# M-LVDS_PHY.net
KiCad netlist of a schematic drawn in Altium Designer
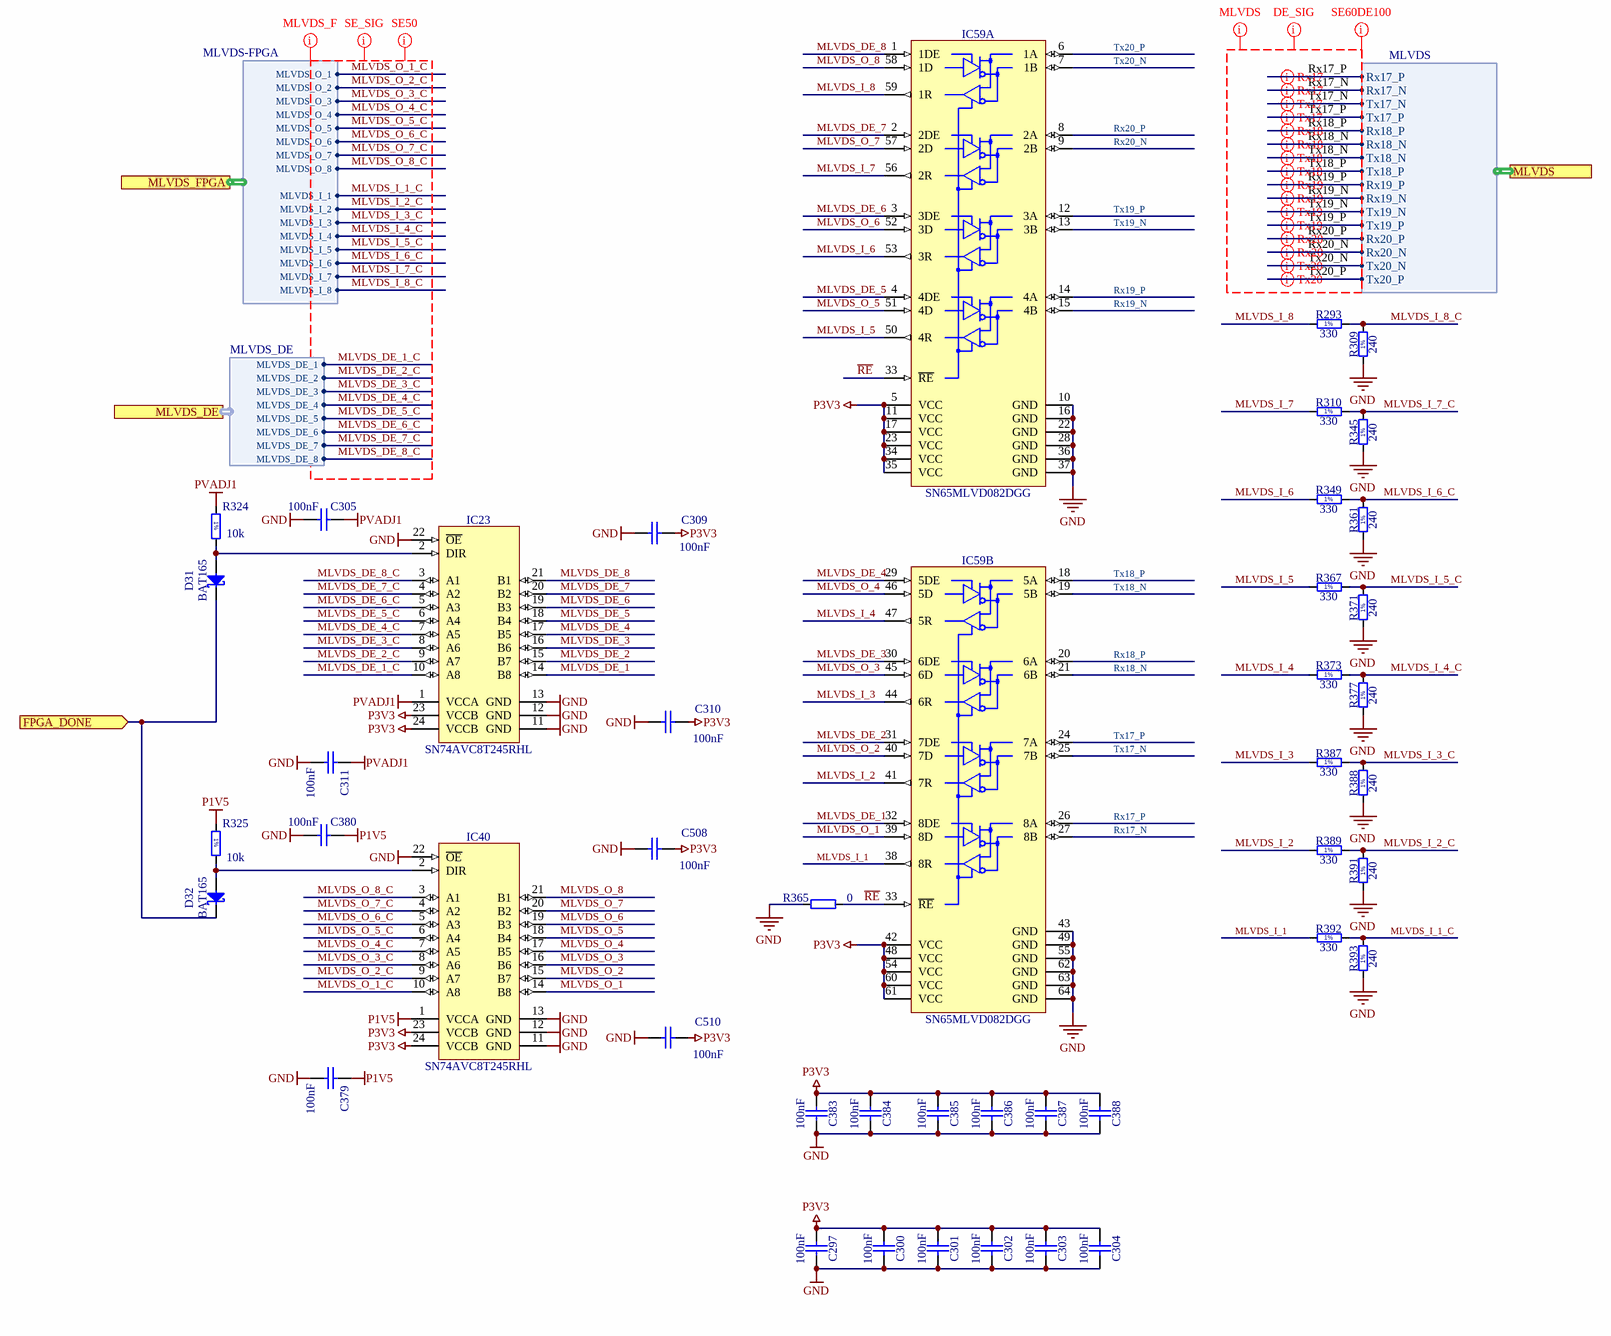
[diagram p0: M-LVDS PHY.SchDoc]

(export (version "E")
  (design (tool "Eeschema 10.0.6"))
  (components
    (comp (ref "C297")
      (value "100nF")
      (footprint "CAPC0603X33N")
      (description "Non-polarised capacitor")
      (fields
        (field (name "PART NUMBER") "CC0201_100NF_6.3V_10%_X5R")
        (field (name "VOLTAGE") "6.3V")
        (field (name "AUTHOR") "CERN DEM JLC")
      )
      (libsource (lib "Capacitors") (part "Capacitor - non polarized"))
    )
    (comp (ref "C300")
      (value "100nF")
      (footprint "CAPC0603X33N")
      (description "Non-polarised capacitor")
      (fields
        (field (name "PART NUMBER") "CC0201_100NF_6.3V_10%_X5R")
        (field (name "VOLTAGE") "6.3V")
        (field (name "AUTHOR") "CERN DEM JLC")
      )
      (libsource (lib "Capacitors") (part "Capacitor - non polarized"))
    )
    (comp (ref "C301")
      (value "100nF")
      (footprint "CAPC0603X33N")
      (description "Non-polarised capacitor")
      (fields
        (field (name "PART NUMBER") "CC0201_100NF_6.3V_10%_X5R")
        (field (name "VOLTAGE") "6.3V")
        (field (name "AUTHOR") "CERN DEM JLC")
      )
      (libsource (lib "Capacitors") (part "Capacitor - non polarized"))
    )
    (comp (ref "C302")
      (value "100nF")
      (footprint "CAPC0603X33N")
      (description "Non-polarised capacitor")
      (fields
        (field (name "PART NUMBER") "CC0201_100NF_6.3V_10%_X5R")
        (field (name "VOLTAGE") "6.3V")
        (field (name "AUTHOR") "CERN DEM JLC")
      )
      (libsource (lib "Capacitors") (part "Capacitor - non polarized"))
    )
    (comp (ref "C303")
      (value "100nF")
      (footprint "CAPC0603X33N")
      (description "Non-polarised capacitor")
      (fields
        (field (name "PART NUMBER") "CC0201_100NF_6.3V_10%_X5R")
        (field (name "VOLTAGE") "6.3V")
        (field (name "AUTHOR") "CERN DEM JLC")
      )
      (libsource (lib "Capacitors") (part "Capacitor - non polarized"))
    )
    (comp (ref "C304")
      (value "100nF")
      (footprint "CAPC0603X33N")
      (description "Non-polarised capacitor")
      (fields
        (field (name "PART NUMBER") "CC0201_100NF_6.3V_10%_X5R")
        (field (name "VOLTAGE") "6.3V")
        (field (name "AUTHOR") "CERN DEM JLC")
      )
      (libsource (lib "Capacitors") (part "Capacitor - non polarized"))
    )
    (comp (ref "C305")
      (value "100nF")
      (footprint "CAPC0603X33N")
      (description "Non-polarised capacitor")
      (fields
        (field (name "PART NUMBER") "CC0201_100NF_6.3V_10%_X5R")
        (field (name "VOLTAGE") "6.3V")
        (field (name "AUTHOR") "CERN DEM JLC")
      )
      (libsource (lib "Capacitors") (part "Capacitor - non polarized"))
    )
    (comp (ref "C309")
      (value "100nF")
      (footprint "CAPC0603X33N")
      (description "Non-polarised capacitor")
      (fields
        (field (name "PART NUMBER") "CC0201_100NF_6.3V_10%_X5R")
        (field (name "VOLTAGE") "6.3V")
        (field (name "AUTHOR") "CERN DEM JLC")
      )
      (libsource (lib "Capacitors") (part "Capacitor - non polarized"))
    )
    (comp (ref "C310")
      (value "100nF")
      (footprint "CAPC0603X33N")
      (description "Non-polarised capacitor")
      (fields
        (field (name "PART NUMBER") "CC0201_100NF_6.3V_10%_X5R")
        (field (name "VOLTAGE") "6.3V")
        (field (name "AUTHOR") "CERN DEM JLC")
      )
      (libsource (lib "Capacitors") (part "Capacitor - non polarized"))
    )
    (comp (ref "C311")
      (value "100nF")
      (footprint "CAPC0603X33N")
      (description "Non-polarised capacitor")
      (fields
        (field (name "PART NUMBER") "CC0201_100NF_6.3V_10%_X5R")
        (field (name "VOLTAGE") "6.3V")
        (field (name "AUTHOR") "CERN DEM JLC")
      )
      (libsource (lib "Capacitors") (part "Capacitor - non polarized"))
    )
    (comp (ref "C379")
      (value "100nF")
      (footprint "CAPC0603X33N")
      (description "Non-polarised capacitor")
      (fields
        (field (name "PART NUMBER") "CC0201_100NF_6.3V_10%_X5R")
        (field (name "VOLTAGE") "6.3V")
        (field (name "AUTHOR") "CERN DEM JLC")
      )
      (libsource (lib "Capacitors") (part "Capacitor - non polarized"))
    )
    (comp (ref "C380")
      (value "100nF")
      (footprint "CAPC0603X33N")
      (description "Non-polarised capacitor")
      (fields
        (field (name "PART NUMBER") "CC0201_100NF_6.3V_10%_X5R")
        (field (name "VOLTAGE") "6.3V")
        (field (name "AUTHOR") "CERN DEM JLC")
      )
      (libsource (lib "Capacitors") (part "Capacitor - non polarized"))
    )
    (comp (ref "C383")
      (value "100nF")
      (footprint "CAPC0603X33N")
      (description "Non-polarised capacitor")
      (fields
        (field (name "PART NUMBER") "CC0201_100NF_6.3V_10%_X5R")
        (field (name "VOLTAGE") "6.3V")
        (field (name "AUTHOR") "CERN DEM JLC")
      )
      (libsource (lib "Capacitors") (part "Capacitor - non polarized"))
    )
    (comp (ref "C384")
      (value "100nF")
      (footprint "CAPC0603X33N")
      (description "Non-polarised capacitor")
      (fields
        (field (name "PART NUMBER") "CC0201_100NF_6.3V_10%_X5R")
        (field (name "VOLTAGE") "6.3V")
        (field (name "AUTHOR") "CERN DEM JLC")
      )
      (libsource (lib "Capacitors") (part "Capacitor - non polarized"))
    )
    (comp (ref "C385")
      (value "100nF")
      (footprint "CAPC0603X33N")
      (description "Non-polarised capacitor")
      (fields
        (field (name "PART NUMBER") "CC0201_100NF_6.3V_10%_X5R")
        (field (name "VOLTAGE") "6.3V")
        (field (name "AUTHOR") "CERN DEM JLC")
      )
      (libsource (lib "Capacitors") (part "Capacitor - non polarized"))
    )
    (comp (ref "C386")
      (value "100nF")
      (footprint "CAPC0603X33N")
      (description "Non-polarised capacitor")
      (fields
        (field (name "PART NUMBER") "CC0201_100NF_6.3V_10%_X5R")
        (field (name "VOLTAGE") "6.3V")
        (field (name "AUTHOR") "CERN DEM JLC")
      )
      (libsource (lib "Capacitors") (part "Capacitor - non polarized"))
    )
    (comp (ref "C387")
      (value "100nF")
      (footprint "CAPC0603X33N")
      (description "Non-polarised capacitor")
      (fields
        (field (name "PART NUMBER") "CC0201_100NF_6.3V_10%_X5R")
        (field (name "VOLTAGE") "6.3V")
        (field (name "AUTHOR") "CERN DEM JLC")
      )
      (libsource (lib "Capacitors") (part "Capacitor - non polarized"))
    )
    (comp (ref "C388")
      (value "100nF")
      (footprint "CAPC0603X33N")
      (description "Non-polarised capacitor")
      (fields
        (field (name "PART NUMBER") "CC0201_100NF_6.3V_10%_X5R")
        (field (name "VOLTAGE") "6.3V")
        (field (name "AUTHOR") "CERN DEM JLC")
      )
      (libsource (lib "Capacitors") (part "Capacitor - non polarized"))
    )
    (comp (ref "C508")
      (value "100nF")
      (footprint "CAPC0603X33N")
      (description "Non-polarised capacitor")
      (fields
        (field (name "PART NUMBER") "CC0201_100NF_6.3V_10%_X5R")
        (field (name "VOLTAGE") "6.3V")
        (field (name "AUTHOR") "CERN DEM JLC")
      )
      (libsource (lib "Capacitors") (part "Capacitor - non polarized"))
    )
    (comp (ref "C510")
      (value "100nF")
      (footprint "CAPC0603X33N")
      (description "Non-polarised capacitor")
      (fields
        (field (name "PART NUMBER") "CC0201_100NF_6.3V_10%_X5R")
        (field (name "VOLTAGE") "6.3V")
        (field (name "AUTHOR") "CERN DEM JLC")
      )
      (libsource (lib "Capacitors") (part "Capacitor - non polarized"))
    )
    (comp (ref "D31")
      (value "BAT165")
      (footprint "SOD2512X110N")
      (description "Schottky Diode")
      (fields
        (field (name "MANUFACTURER") "INFINEON")
        (field (name "VOLTAGE") "40V")
        (field (name "AUTHOR") "CERN DEM JLC")
      )
      (libsource (lib "ICs And Semiconductors") (part "Diode Schottky"))
    )
    (comp (ref "D32")
      (value "BAT165")
      (footprint "SOD2512X110N")
      (description "Schottky Diode")
      (fields
        (field (name "MANUFACTURER") "INFINEON")
        (field (name "VOLTAGE") "40V")
        (field (name "AUTHOR") "CERN DEM JLC")
      )
      (libsource (lib "ICs And Semiconductors") (part "Diode Schottky"))
    )
    (comp (ref "IC23")
      (value "SN74AVC8T245RHL")
      (footprint "TEXAS_RHL (S-PVQFN-N24)")
      (description "8-Bit Dual-Supply Bus Transceiver With Configurable Voltage Translation and 3-State Outputs")
      (fields (field (name "MANUFACTURER") "TEXAS INSTRUMENTS") (field (name "AUTHOR") "CERN DEM MR"))
      (libsource (lib "ICs And Semiconductors") (part "748T245"))
    )
    (comp (ref "IC40")
      (value "SN74AVC8T245RHL")
      (footprint "TEXAS_RHL (S-PVQFN-N24)")
      (description "8-Bit Dual-Supply Bus Transceiver With Configurable Voltage Translation and 3-State Outputs")
      (fields (field (name "MANUFACTURER") "TEXAS INSTRUMENTS") (field (name "AUTHOR") "CERN DEM MR"))
      (libsource (lib "ICs And Semiconductors") (part "748T245"))
    )
    (comp (ref "IC59")
      (value "SN65MLVD082DGG")
      (footprint "SOP50P810X120-64N")
      (description "8-Channel Half-Duplex M-LVDS Line Transceiver")
      (fields (field (name "MANUFACTURER") "TEXAS INSTRUMENTS") (field (name "AUTHOR") "CERN DEM BC"))
      (libsource (lib "ICs And Semiconductors") (part "SN65MLVD082"))
    )
    (comp (ref "R293")
      (value "330")
      (footprint "RESC1005X40N")
      (description "Resistor - 1%")
      (fields
        (field (name "PART NUMBER") "R0402_330R_1%_0.0625W_100PPM")
        (field (name "POWER") "0.0625W")
        (field (name "AUTHOR") "CERN DEM JLC")
      )
      (libsource (lib "Resistors") (part "Resistor - 1%"))
    )
    (comp (ref "R309")
      (value "240")
      (footprint "RESC1005X40N")
      (description "Resistor - 1%")
      (fields
        (field (name "PART NUMBER") "R0402_240R_1%_0.0625W_100PPM")
        (field (name "POWER") "0.0625W")
        (field (name "AUTHOR") "CERN DEM JLC")
      )
      (libsource (lib "Resistors") (part "Resistor - 1%"))
    )
    (comp (ref "R310")
      (value "330")
      (footprint "RESC1005X40N")
      (description "Resistor - 1%")
      (fields
        (field (name "PART NUMBER") "R0402_330R_1%_0.0625W_100PPM")
        (field (name "POWER") "0.0625W")
        (field (name "AUTHOR") "CERN DEM JLC")
      )
      (libsource (lib "Resistors") (part "Resistor - 1%"))
    )
    (comp (ref "R324")
      (value "10k")
      (footprint "RESC1005X40N")
      (description "Resistor - 1%")
      (fields
        (field (name "PART NUMBER") "R0402_10K_1%_0.0625W_100PPM")
        (field (name "POWER") "0.0625W")
        (field (name "AUTHOR") "CERN DEM JLC")
      )
      (libsource (lib "Resistors") (part "Resistor - 1%"))
    )
    (comp (ref "R325")
      (value "10k")
      (footprint "RESC1005X40N")
      (description "Resistor - 1%")
      (fields
        (field (name "PART NUMBER") "R0402_10K_1%_0.0625W_100PPM")
        (field (name "POWER") "0.0625W")
        (field (name "AUTHOR") "CERN DEM JLC")
      )
      (libsource (lib "Resistors") (part "Resistor - 1%"))
    )
    (comp (ref "R345")
      (value "240")
      (footprint "RESC1005X40N")
      (description "Resistor - 1%")
      (fields
        (field (name "PART NUMBER") "R0402_240R_1%_0.0625W_100PPM")
        (field (name "POWER") "0.0625W")
        (field (name "AUTHOR") "CERN DEM JLC")
      )
      (libsource (lib "Resistors") (part "Resistor - 1%"))
    )
    (comp (ref "R349")
      (value "330")
      (footprint "RESC1005X40N")
      (description "Resistor - 1%")
      (fields
        (field (name "PART NUMBER") "R0402_330R_1%_0.0625W_100PPM")
        (field (name "POWER") "0.0625W")
        (field (name "AUTHOR") "CERN DEM JLC")
      )
      (libsource (lib "Resistors") (part "Resistor - 1%"))
    )
    (comp (ref "R361")
      (value "240")
      (footprint "RESC1005X40N")
      (description "Resistor - 1%")
      (fields
        (field (name "PART NUMBER") "R0402_240R_1%_0.0625W_100PPM")
        (field (name "POWER") "0.0625W")
        (field (name "AUTHOR") "CERN DEM JLC")
      )
      (libsource (lib "Resistors") (part "Resistor - 1%"))
    )
    (comp (ref "R365")
      (value "0")
      (footprint "RESC0603X28N")
      (description "Resistor")
      (fields
        (field (name "PART NUMBER") "R0201_0R_JUMPER")
        (field (name "MANUFACTURER") "GENERIC")
        (field (name "AUTHOR") "CERN DEM JLC")
      )
      (libsource (lib "Resistors") (part "Resistor"))
    )
    (comp (ref "R367")
      (value "330")
      (footprint "RESC1005X40N")
      (description "Resistor - 1%")
      (fields
        (field (name "PART NUMBER") "R0402_330R_1%_0.0625W_100PPM")
        (field (name "POWER") "0.0625W")
        (field (name "AUTHOR") "CERN DEM JLC")
      )
      (libsource (lib "Resistors") (part "Resistor - 1%"))
    )
    (comp (ref "R371")
      (value "240")
      (footprint "RESC1005X40N")
      (description "Resistor - 1%")
      (fields
        (field (name "PART NUMBER") "R0402_240R_1%_0.0625W_100PPM")
        (field (name "POWER") "0.0625W")
        (field (name "AUTHOR") "CERN DEM JLC")
      )
      (libsource (lib "Resistors") (part "Resistor - 1%"))
    )
    (comp (ref "R373")
      (value "330")
      (footprint "RESC1005X40N")
      (description "Resistor - 1%")
      (fields
        (field (name "PART NUMBER") "R0402_330R_1%_0.0625W_100PPM")
        (field (name "POWER") "0.0625W")
        (field (name "AUTHOR") "CERN DEM JLC")
      )
      (libsource (lib "Resistors") (part "Resistor - 1%"))
    )
    (comp (ref "R377")
      (value "240")
      (footprint "RESC1005X40N")
      (description "Resistor - 1%")
      (fields
        (field (name "PART NUMBER") "R0402_240R_1%_0.0625W_100PPM")
        (field (name "POWER") "0.0625W")
        (field (name "AUTHOR") "CERN DEM JLC")
      )
      (libsource (lib "Resistors") (part "Resistor - 1%"))
    )
    (comp (ref "R387")
      (value "330")
      (footprint "RESC1005X40N")
      (description "Resistor - 1%")
      (fields
        (field (name "PART NUMBER") "R0402_330R_1%_0.0625W_100PPM")
        (field (name "POWER") "0.0625W")
        (field (name "AUTHOR") "CERN DEM JLC")
      )
      (libsource (lib "Resistors") (part "Resistor - 1%"))
    )
    (comp (ref "R388")
      (value "240")
      (footprint "RESC1005X40N")
      (description "Resistor - 1%")
      (fields
        (field (name "PART NUMBER") "R0402_240R_1%_0.0625W_100PPM")
        (field (name "POWER") "0.0625W")
        (field (name "AUTHOR") "CERN DEM JLC")
      )
      (libsource (lib "Resistors") (part "Resistor - 1%"))
    )
    (comp (ref "R389")
      (value "330")
      (footprint "RESC1005X40N")
      (description "Resistor - 1%")
      (fields
        (field (name "PART NUMBER") "R0402_330R_1%_0.0625W_100PPM")
        (field (name "POWER") "0.0625W")
        (field (name "AUTHOR") "CERN DEM JLC")
      )
      (libsource (lib "Resistors") (part "Resistor - 1%"))
    )
    (comp (ref "R391")
      (value "240")
      (footprint "RESC1005X40N")
      (description "Resistor - 1%")
      (fields
        (field (name "PART NUMBER") "R0402_240R_1%_0.0625W_100PPM")
        (field (name "POWER") "0.0625W")
        (field (name "AUTHOR") "CERN DEM JLC")
      )
      (libsource (lib "Resistors") (part "Resistor - 1%"))
    )
    (comp (ref "R392")
      (value "330")
      (footprint "RESC1005X40N")
      (description "Resistor - 1%")
      (fields
        (field (name "PART NUMBER") "R0402_330R_1%_0.0625W_100PPM")
        (field (name "POWER") "0.0625W")
        (field (name "AUTHOR") "CERN DEM JLC")
      )
      (libsource (lib "Resistors") (part "Resistor - 1%"))
    )
    (comp (ref "R393")
      (value "240")
      (footprint "RESC1005X40N")
      (description "Resistor - 1%")
      (fields
        (field (name "PART NUMBER") "R0402_240R_1%_0.0625W_100PPM")
        (field (name "POWER") "0.0625W")
        (field (name "AUTHOR") "CERN DEM JLC")
      )
      (libsource (lib "Resistors") (part "Resistor - 1%"))
    )
  )
  (nets
    (net (code "4") (name "/FPGA_DONE") (class "Default")
      (node (ref "D31") (pin "1") (pinfunction "C_1") (pintype "passive"))
      (node (ref "D32") (pin "1") (pinfunction "C_1") (pintype "passive"))
    )
    (net (code "5") (name "/MLVDS_DE_1") (class "Default")
      (node (ref "IC23") (pin "14") (pinfunction "B8_14") (pintype "bidirectional"))
      (node (ref "IC59") (pin "32") (pinfunction "8DE_32") (pintype "input"))
    )
    (net (code "6") (name "/MLVDS_DE_1_C") (class "Default")
      (node (ref "IC23") (pin "10") (pinfunction "A8_10") (pintype "bidirectional"))
    )
    (net (code "7") (name "/MLVDS_DE_2") (class "Default")
      (node (ref "IC23") (pin "15") (pinfunction "B7_15") (pintype "bidirectional"))
      (node (ref "IC59") (pin "31") (pinfunction "7DE_31") (pintype "input"))
    )
    (net (code "8") (name "/MLVDS_DE_2_C") (class "Default")
      (node (ref "IC23") (pin "9") (pinfunction "A7_9") (pintype "bidirectional"))
    )
    (net (code "9") (name "/MLVDS_DE_3") (class "Default")
      (node (ref "IC23") (pin "16") (pinfunction "B6_16") (pintype "bidirectional"))
      (node (ref "IC59") (pin "30") (pinfunction "6DE_30") (pintype "input"))
    )
    (net (code "10") (name "/MLVDS_DE_3_C") (class "Default")
      (node (ref "IC23") (pin "8") (pinfunction "A6_8") (pintype "bidirectional"))
    )
    (net (code "11") (name "/MLVDS_DE_4") (class "Default")
      (node (ref "IC23") (pin "17") (pinfunction "B5_17") (pintype "bidirectional"))
      (node (ref "IC59") (pin "29") (pinfunction "5DE_29") (pintype "input"))
    )
    (net (code "12") (name "/MLVDS_DE_4_C") (class "Default")
      (node (ref "IC23") (pin "7") (pinfunction "A5_7") (pintype "bidirectional"))
    )
    (net (code "13") (name "/MLVDS_DE_5") (class "Default")
      (node (ref "IC23") (pin "18") (pinfunction "B4_18") (pintype "bidirectional"))
      (node (ref "IC59") (pin "4") (pinfunction "4DE_4") (pintype "input"))
    )
    (net (code "14") (name "/MLVDS_DE_5_C") (class "Default")
      (node (ref "IC23") (pin "6") (pinfunction "A4_6") (pintype "bidirectional"))
    )
    (net (code "15") (name "/MLVDS_DE_6") (class "Default")
      (node (ref "IC23") (pin "19") (pinfunction "B3_19") (pintype "bidirectional"))
      (node (ref "IC59") (pin "3") (pinfunction "3DE_3") (pintype "input"))
    )
    (net (code "16") (name "/MLVDS_DE_6_C") (class "Default")
      (node (ref "IC23") (pin "5") (pinfunction "A3_5") (pintype "bidirectional"))
    )
    (net (code "17") (name "/MLVDS_DE_7") (class "Default")
      (node (ref "IC23") (pin "20") (pinfunction "B2_20") (pintype "bidirectional"))
      (node (ref "IC59") (pin "2") (pinfunction "2DE_2") (pintype "input"))
    )
    (net (code "18") (name "/MLVDS_DE_7_C") (class "Default")
      (node (ref "IC23") (pin "4") (pinfunction "A2_4") (pintype "bidirectional"))
    )
    (net (code "19") (name "/MLVDS_DE_8") (class "Default")
      (node (ref "IC23") (pin "21") (pinfunction "B1_21") (pintype "bidirectional"))
      (node (ref "IC59") (pin "1") (pinfunction "1DE_1") (pintype "input"))
    )
    (net (code "20") (name "/MLVDS_DE_8_C") (class "Default")
      (node (ref "IC23") (pin "3") (pinfunction "A1_3") (pintype "bidirectional"))
    )
    (net (code "21") (name "/MLVDS_I_1") (class "Default")
      (node (ref "IC59") (pin "38") (pinfunction "8R_38") (pintype "output"))
      (node (ref "R392") (pin "1") (pinfunction "1_1") (pintype "passive"))
    )
    (net (code "22") (name "/MLVDS_I_1_C") (class "Default")
      (node (ref "R392") (pin "2") (pinfunction "2_2") (pintype "passive"))
      (node (ref "R393") (pin "2") (pinfunction "2_2") (pintype "passive"))
    )
    (net (code "23") (name "/MLVDS_I_2") (class "Default")
      (node (ref "IC59") (pin "41") (pinfunction "7R_41") (pintype "output"))
      (node (ref "R389") (pin "1") (pinfunction "1_1") (pintype "passive"))
    )
    (net (code "24") (name "/MLVDS_I_2_C") (class "Default")
      (node (ref "R389") (pin "2") (pinfunction "2_2") (pintype "passive"))
      (node (ref "R391") (pin "2") (pinfunction "2_2") (pintype "passive"))
    )
    (net (code "25") (name "/MLVDS_I_3") (class "Default")
      (node (ref "IC59") (pin "44") (pinfunction "6R_44") (pintype "output"))
      (node (ref "R387") (pin "1") (pinfunction "1_1") (pintype "passive"))
    )
    (net (code "26") (name "/MLVDS_I_3_C") (class "Default")
      (node (ref "R387") (pin "2") (pinfunction "2_2") (pintype "passive"))
      (node (ref "R388") (pin "2") (pinfunction "2_2") (pintype "passive"))
    )
    (net (code "27") (name "/MLVDS_I_4") (class "Default")
      (node (ref "IC59") (pin "47") (pinfunction "5R_47") (pintype "output"))
      (node (ref "R373") (pin "1") (pinfunction "1_1") (pintype "passive"))
    )
    (net (code "28") (name "/MLVDS_I_4_C") (class "Default")
      (node (ref "R373") (pin "2") (pinfunction "2_2") (pintype "passive"))
      (node (ref "R377") (pin "2") (pinfunction "2_2") (pintype "passive"))
    )
    (net (code "29") (name "/MLVDS_I_5") (class "Default")
      (node (ref "IC59") (pin "50") (pinfunction "4R_50") (pintype "output"))
      (node (ref "R367") (pin "1") (pinfunction "1_1") (pintype "passive"))
    )
    (net (code "30") (name "/MLVDS_I_5_C") (class "Default")
      (node (ref "R367") (pin "2") (pinfunction "2_2") (pintype "passive"))
      (node (ref "R371") (pin "2") (pinfunction "2_2") (pintype "passive"))
    )
    (net (code "31") (name "/MLVDS_I_6") (class "Default")
      (node (ref "IC59") (pin "53") (pinfunction "3R_53") (pintype "output"))
      (node (ref "R349") (pin "1") (pinfunction "1_1") (pintype "passive"))
    )
    (net (code "32") (name "/MLVDS_I_6_C") (class "Default")
      (node (ref "R349") (pin "2") (pinfunction "2_2") (pintype "passive"))
      (node (ref "R361") (pin "2") (pinfunction "2_2") (pintype "passive"))
    )
    (net (code "33") (name "/MLVDS_I_7") (class "Default")
      (node (ref "IC59") (pin "56") (pinfunction "2R_56") (pintype "output"))
      (node (ref "R310") (pin "1") (pinfunction "1_1") (pintype "passive"))
    )
    (net (code "34") (name "/MLVDS_I_7_C") (class "Default")
      (node (ref "R310") (pin "2") (pinfunction "2_2") (pintype "passive"))
      (node (ref "R345") (pin "2") (pinfunction "2_2") (pintype "passive"))
    )
    (net (code "35") (name "/MLVDS_I_8") (class "Default")
      (node (ref "IC59") (pin "59") (pinfunction "1R_59") (pintype "output"))
      (node (ref "R293") (pin "1") (pinfunction "1_1") (pintype "passive"))
    )
    (net (code "36") (name "/MLVDS_I_8_C") (class "Default")
      (node (ref "R293") (pin "2") (pinfunction "2_2") (pintype "passive"))
      (node (ref "R309") (pin "2") (pinfunction "2_2") (pintype "passive"))
    )
    (net (code "37") (name "/MLVDS_O_1") (class "Default")
      (node (ref "IC40") (pin "14") (pinfunction "B8_14") (pintype "bidirectional"))
      (node (ref "IC59") (pin "39") (pinfunction "8D_39") (pintype "input"))
    )
    (net (code "38") (name "/MLVDS_O_1_C") (class "Default")
      (node (ref "IC40") (pin "10") (pinfunction "A8_10") (pintype "bidirectional"))
    )
    (net (code "39") (name "/MLVDS_O_2") (class "Default")
      (node (ref "IC40") (pin "15") (pinfunction "B7_15") (pintype "bidirectional"))
      (node (ref "IC59") (pin "40") (pinfunction "7D_40") (pintype "input"))
    )
    (net (code "40") (name "/MLVDS_O_2_C") (class "Default")
      (node (ref "IC40") (pin "9") (pinfunction "A7_9") (pintype "bidirectional"))
    )
    (net (code "41") (name "/MLVDS_O_3") (class "Default")
      (node (ref "IC40") (pin "16") (pinfunction "B6_16") (pintype "bidirectional"))
      (node (ref "IC59") (pin "45") (pinfunction "6D_45") (pintype "input"))
    )
    (net (code "42") (name "/MLVDS_O_3_C") (class "Default")
      (node (ref "IC40") (pin "8") (pinfunction "A6_8") (pintype "bidirectional"))
    )
    (net (code "43") (name "/MLVDS_O_4") (class "Default")
      (node (ref "IC40") (pin "17") (pinfunction "B5_17") (pintype "bidirectional"))
      (node (ref "IC59") (pin "46") (pinfunction "5D_46") (pintype "input"))
    )
    (net (code "44") (name "/MLVDS_O_4_C") (class "Default")
      (node (ref "IC40") (pin "7") (pinfunction "A5_7") (pintype "bidirectional"))
    )
    (net (code "45") (name "/MLVDS_O_5") (class "Default")
      (node (ref "IC40") (pin "18") (pinfunction "B4_18") (pintype "bidirectional"))
      (node (ref "IC59") (pin "51") (pinfunction "4D_51") (pintype "input"))
    )
    (net (code "46") (name "/MLVDS_O_5_C") (class "Default")
      (node (ref "IC40") (pin "6") (pinfunction "A4_6") (pintype "bidirectional"))
    )
    (net (code "47") (name "/MLVDS_O_6") (class "Default")
      (node (ref "IC40") (pin "19") (pinfunction "B3_19") (pintype "bidirectional"))
      (node (ref "IC59") (pin "52") (pinfunction "3D_52") (pintype "input"))
    )
    (net (code "48") (name "/MLVDS_O_6_C") (class "Default")
      (node (ref "IC40") (pin "5") (pinfunction "A3_5") (pintype "bidirectional"))
    )
    (net (code "49") (name "/MLVDS_O_7") (class "Default")
      (node (ref "IC40") (pin "20") (pinfunction "B2_20") (pintype "bidirectional"))
      (node (ref "IC59") (pin "57") (pinfunction "2D_57") (pintype "input"))
    )
    (net (code "50") (name "/MLVDS_O_7_C") (class "Default")
      (node (ref "IC40") (pin "4") (pinfunction "A2_4") (pintype "bidirectional"))
    )
    (net (code "51") (name "/MLVDS_O_8") (class "Default")
      (node (ref "IC40") (pin "21") (pinfunction "B1_21") (pintype "bidirectional"))
      (node (ref "IC59") (pin "58") (pinfunction "1D_58") (pintype "input"))
    )
    (net (code "52") (name "/MLVDS_O_8_C") (class "Default")
      (node (ref "IC40") (pin "3") (pinfunction "A1_3") (pintype "bidirectional"))
    )
    (net (code "53") (name "/Rx17_N") (class "Default")
      (node (ref "IC59") (pin "27") (pinfunction "8B_27") (pintype "bidirectional"))
    )
    (net (code "54") (name "/Rx17_P") (class "Default")
      (node (ref "IC59") (pin "26") (pinfunction "8A_26") (pintype "bidirectional"))
    )
    (net (code "55") (name "/Rx18_N") (class "Default")
      (node (ref "IC59") (pin "21") (pinfunction "6B_21") (pintype "bidirectional"))
    )
    (net (code "56") (name "/Rx18_P") (class "Default")
      (node (ref "IC59") (pin "20") (pinfunction "6A_20") (pintype "bidirectional"))
    )
    (net (code "57") (name "/Rx19_N") (class "Default")
      (node (ref "IC59") (pin "15") (pinfunction "4B_15") (pintype "bidirectional"))
    )
    (net (code "58") (name "/Rx19_P") (class "Default")
      (node (ref "IC59") (pin "14") (pinfunction "4A_14") (pintype "bidirectional"))
    )
    (net (code "59") (name "/Rx20_N") (class "Default")
      (node (ref "IC59") (pin "9") (pinfunction "2B_9") (pintype "bidirectional"))
    )
    (net (code "60") (name "/Rx20_P") (class "Default")
      (node (ref "IC59") (pin "8") (pinfunction "2A_8") (pintype "bidirectional"))
    )
    (net (code "61") (name "/Tx17_N") (class "Default")
      (node (ref "IC59") (pin "25") (pinfunction "7B_25") (pintype "bidirectional"))
    )
    (net (code "62") (name "/Tx17_P") (class "Default")
      (node (ref "IC59") (pin "24") (pinfunction "7A_24") (pintype "bidirectional"))
    )
    (net (code "63") (name "/Tx18_N") (class "Default")
      (node (ref "IC59") (pin "19") (pinfunction "5B_19") (pintype "bidirectional"))
    )
    (net (code "64") (name "/Tx18_P") (class "Default")
      (node (ref "IC59") (pin "18") (pinfunction "5A_18") (pintype "bidirectional"))
    )
    (net (code "65") (name "/Tx19_N") (class "Default")
      (node (ref "IC59") (pin "13") (pinfunction "3B_13") (pintype "bidirectional"))
    )
    (net (code "66") (name "/Tx19_P") (class "Default")
      (node (ref "IC59") (pin "12") (pinfunction "3A_12") (pintype "bidirectional"))
    )
    (net (code "67") (name "/Tx20_N") (class "Default")
      (node (ref "IC59") (pin "7") (pinfunction "1B_7") (pintype "bidirectional"))
    )
    (net (code "68") (name "/Tx20_P") (class "Default")
      (node (ref "IC59") (pin "6") (pinfunction "1A_6") (pintype "bidirectional"))
    )
    (net (code "72") (name "/~{RE}") (class "Default")
      (node (ref "IC59") (pin "33") (pinfunction "~{RE}_33") (pintype "input"))
      (node (ref "R365") (pin "2") (pinfunction "2_2") (pintype "passive"))
    )
    (net (code "73") (name "GND") (class "Default")
      (node (ref "C297") (pin "2") (pinfunction "2_2") (pintype "passive"))
      (node (ref "C300") (pin "2") (pinfunction "2_2") (pintype "passive"))
      (node (ref "C301") (pin "2") (pinfunction "2_2") (pintype "passive"))
      (node (ref "C302") (pin "2") (pinfunction "2_2") (pintype "passive"))
      (node (ref "C303") (pin "2") (pinfunction "2_2") (pintype "passive"))
      (node (ref "C304") (pin "2") (pinfunction "2_2") (pintype "passive"))
      (node (ref "C305") (pin "1") (pinfunction "1_1") (pintype "passive"))
      (node (ref "C309") (pin "2") (pinfunction "2_2") (pintype "passive"))
      (node (ref "C310") (pin "2") (pinfunction "2_2") (pintype "passive"))
      (node (ref "C311") (pin "1") (pinfunction "1_1") (pintype "passive"))
      (node (ref "C379") (pin "1") (pinfunction "1_1") (pintype "passive"))
      (node (ref "C380") (pin "1") (pinfunction "1_1") (pintype "passive"))
      (node (ref "C383") (pin "2") (pinfunction "2_2") (pintype "passive"))
      (node (ref "C384") (pin "2") (pinfunction "2_2") (pintype "passive"))
      (node (ref "C385") (pin "2") (pinfunction "2_2") (pintype "passive"))
      (node (ref "C386") (pin "2") (pinfunction "2_2") (pintype "passive"))
      (node (ref "C387") (pin "2") (pinfunction "2_2") (pintype "passive"))
      (node (ref "C388") (pin "2") (pinfunction "2_2") (pintype "passive"))
      (node (ref "C508") (pin "2") (pinfunction "2_2") (pintype "passive"))
      (node (ref "C510") (pin "2") (pinfunction "2_2") (pintype "passive"))
      (node (ref "IC23") (pin "11") (pinfunction "GND_11") (pintype "power_in"))
      (node (ref "IC23") (pin "12") (pinfunction "GND_12") (pintype "power_in"))
      (node (ref "IC23") (pin "13") (pinfunction "GND_13") (pintype "power_in"))
      (node (ref "IC23") (pin "22") (pinfunction "~{OE}_22") (pintype "input"))
      (node (ref "IC40") (pin "11") (pinfunction "GND_11") (pintype "power_in"))
      (node (ref "IC40") (pin "12") (pinfunction "GND_12") (pintype "power_in"))
      (node (ref "IC40") (pin "13") (pinfunction "GND_13") (pintype "power_in"))
      (node (ref "IC40") (pin "22") (pinfunction "~{OE}_22") (pintype "input"))
      (node (ref "IC59") (pin "10") (pinfunction "GND_10") (pintype "power_in"))
      (node (ref "IC59") (pin "16") (pinfunction "GND_16") (pintype "power_in"))
      (node (ref "IC59") (pin "22") (pinfunction "GND_22") (pintype "power_in"))
      (node (ref "IC59") (pin "28") (pinfunction "GND_28") (pintype "power_in"))
      (node (ref "IC59") (pin "36") (pinfunction "GND_36") (pintype "power_in"))
      (node (ref "IC59") (pin "37") (pinfunction "GND_37") (pintype "power_in"))
      (node (ref "IC59") (pin "43") (pinfunction "GND_43") (pintype "power_in"))
      (node (ref "IC59") (pin "49") (pinfunction "GND_49") (pintype "power_in"))
      (node (ref "IC59") (pin "55") (pinfunction "GND_55") (pintype "power_in"))
      (node (ref "IC59") (pin "62") (pinfunction "GND_62") (pintype "power_in"))
      (node (ref "IC59") (pin "63") (pinfunction "GND_63") (pintype "power_in"))
      (node (ref "IC59") (pin "64") (pinfunction "GND_64") (pintype "power_in"))
      (node (ref "R309") (pin "1") (pinfunction "1_1") (pintype "passive"))
      (node (ref "R345") (pin "1") (pinfunction "1_1") (pintype "passive"))
      (node (ref "R361") (pin "1") (pinfunction "1_1") (pintype "passive"))
      (node (ref "R365") (pin "1") (pinfunction "1_1") (pintype "passive"))
      (node (ref "R371") (pin "1") (pinfunction "1_1") (pintype "passive"))
      (node (ref "R377") (pin "1") (pinfunction "1_1") (pintype "passive"))
      (node (ref "R388") (pin "1") (pinfunction "1_1") (pintype "passive"))
      (node (ref "R391") (pin "1") (pinfunction "1_1") (pintype "passive"))
      (node (ref "R393") (pin "1") (pinfunction "1_1") (pintype "passive"))
    )
    (net (code "74") (name "Net-(D31-A)") (class "Default")
      (node (ref "D31") (pin "2") (pinfunction "A_2") (pintype "passive"))
      (node (ref "IC23") (pin "2") (pinfunction "DIR_2") (pintype "input"))
      (node (ref "R324") (pin "2") (pinfunction "2_2") (pintype "passive"))
    )
    (net (code "75") (name "Net-(D32-A)") (class "Default")
      (node (ref "D32") (pin "2") (pinfunction "A_2") (pintype "passive"))
      (node (ref "IC40") (pin "2") (pinfunction "DIR_2") (pintype "input"))
      (node (ref "R325") (pin "2") (pinfunction "2_2") (pintype "passive"))
    )
    (net (code "76") (name "P1V5") (class "Default")
      (node (ref "C379") (pin "2") (pinfunction "2_2") (pintype "passive"))
      (node (ref "C380") (pin "2") (pinfunction "2_2") (pintype "passive"))
      (node (ref "IC40") (pin "1") (pinfunction "VCCA_1") (pintype "power_in"))
      (node (ref "R325") (pin "1") (pinfunction "1_1") (pintype "passive"))
    )
    (net (code "77") (name "P3V3") (class "Default")
      (node (ref "C297") (pin "1") (pinfunction "1_1") (pintype "passive"))
      (node (ref "C300") (pin "1") (pinfunction "1_1") (pintype "passive"))
      (node (ref "C301") (pin "1") (pinfunction "1_1") (pintype "passive"))
      (node (ref "C302") (pin "1") (pinfunction "1_1") (pintype "passive"))
      (node (ref "C303") (pin "1") (pinfunction "1_1") (pintype "passive"))
      (node (ref "C304") (pin "1") (pinfunction "1_1") (pintype "passive"))
      (node (ref "C309") (pin "1") (pinfunction "1_1") (pintype "passive"))
      (node (ref "C310") (pin "1") (pinfunction "1_1") (pintype "passive"))
      (node (ref "C383") (pin "1") (pinfunction "1_1") (pintype "passive"))
      (node (ref "C384") (pin "1") (pinfunction "1_1") (pintype "passive"))
      (node (ref "C385") (pin "1") (pinfunction "1_1") (pintype "passive"))
      (node (ref "C386") (pin "1") (pinfunction "1_1") (pintype "passive"))
      (node (ref "C387") (pin "1") (pinfunction "1_1") (pintype "passive"))
      (node (ref "C388") (pin "1") (pinfunction "1_1") (pintype "passive"))
      (node (ref "C508") (pin "1") (pinfunction "1_1") (pintype "passive"))
      (node (ref "C510") (pin "1") (pinfunction "1_1") (pintype "passive"))
      (node (ref "IC23") (pin "23") (pinfunction "VCCB_23") (pintype "power_in"))
      (node (ref "IC23") (pin "24") (pinfunction "VCCB_24") (pintype "power_in"))
      (node (ref "IC40") (pin "23") (pinfunction "VCCB_23") (pintype "power_in"))
      (node (ref "IC40") (pin "24") (pinfunction "VCCB_24") (pintype "power_in"))
      (node (ref "IC59") (pin "11") (pinfunction "VCC_11") (pintype "power_in"))
      (node (ref "IC59") (pin "17") (pinfunction "VCC_17") (pintype "power_in"))
      (node (ref "IC59") (pin "23") (pinfunction "VCC_23") (pintype "power_in"))
      (node (ref "IC59") (pin "34") (pinfunction "VCC_34") (pintype "power_in"))
      (node (ref "IC59") (pin "35") (pinfunction "VCC_35") (pintype "power_in"))
      (node (ref "IC59") (pin "42") (pinfunction "VCC_42") (pintype "power_in"))
      (node (ref "IC59") (pin "48") (pinfunction "VCC_48") (pintype "power_in"))
      (node (ref "IC59") (pin "5") (pinfunction "VCC_5") (pintype "power_in"))
      (node (ref "IC59") (pin "54") (pinfunction "VCC_54") (pintype "power_in"))
      (node (ref "IC59") (pin "60") (pinfunction "VCC_60") (pintype "power_in"))
      (node (ref "IC59") (pin "61") (pinfunction "VCC_61") (pintype "power_in"))
    )
    (net (code "78") (name "PVADJ1") (class "Default")
      (node (ref "C305") (pin "2") (pinfunction "2_2") (pintype "passive"))
      (node (ref "C311") (pin "2") (pinfunction "2_2") (pintype "passive"))
      (node (ref "IC23") (pin "1") (pinfunction "VCCA_1") (pintype "power_in"))
      (node (ref "R324") (pin "1") (pinfunction "1_1") (pintype "passive"))
    )
  )
)
